# COM_R_manufactured.net
KiCad netlist of a schematic drawn in EAGLE
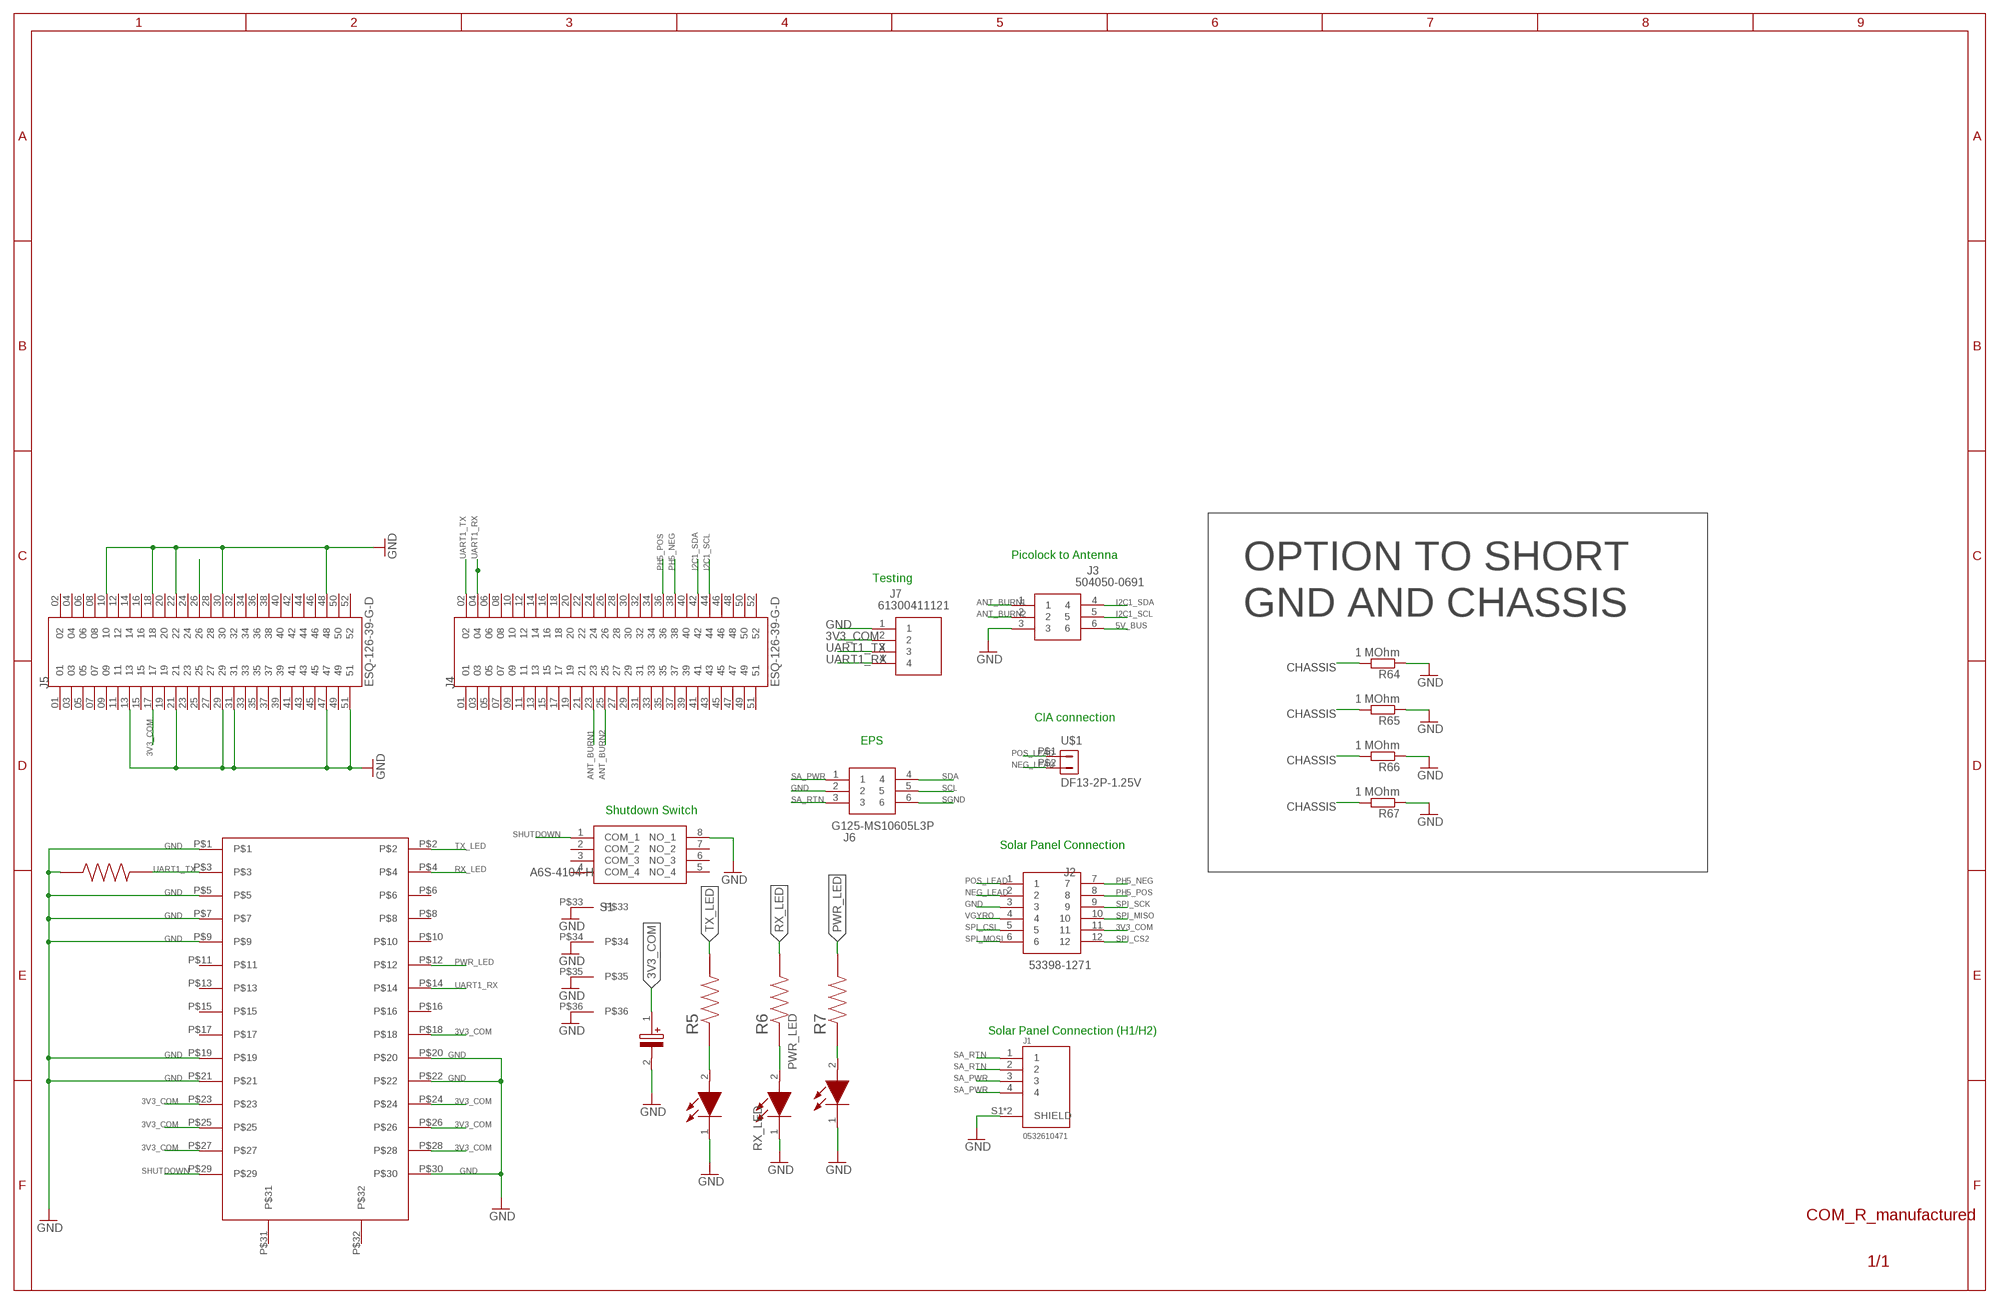
[diagram p0: schematic, sheet 1]

(export (version "E")
  (design (tool "Eeschema 10.0.6"))
  (components
    (comp (ref "C2")
      (value "293D106X0010A2TE3")
      (footprint "eagle-import:CAPPM3216X180N")
      (fields (field (name "MOUSER_PART_NUMBER") "74-293D106X0010A2TE3"))
      (libsource (lib "eagle-import") (part "293D106X0010A2TE3"))
    )
    (comp (ref "J1")
      (value "0532610471")
      (footprint "eagle-import:MOLEX_0532610471")
      (fields (field (name "MF") "Molex"))
      (libsource (lib "eagle-import") (part "0532610471"))
    )
    (comp (ref "J2")
      (value "53398-1271")
      (footprint "eagle-import:53398-1271")
      (fields (field (name "MOUSER_PART_NUMBER") "538-53398-1271"))
      (libsource (lib "eagle-import") (part "53398-1271"))
    )
    (comp (ref "J3")
      (value "504050-0691")
      (footprint "eagle-import:504050-0691_2")
      (fields (field (name "MOUSER_PART_NUMBER") "538-504050-0691"))
      (libsource (lib "eagle-import") (part "504050-0691"))
    )
    (comp (ref "J4")
      (value "ESQ-126-39-G-D")
      (footprint "eagle-import:SAMTEC_ESQ-126-39-G-D")
      (fields (field (name "MF") "Samtec"))
      (libsource (lib "eagle-import") (part "ESQ-126-39-G-D"))
    )
    (comp (ref "J5")
      (value "ESQ-126-39-G-D")
      (footprint "eagle-import:SAMTEC_ESQ-126-39-G-D")
      (fields (field (name "MF") "Samtec"))
      (libsource (lib "eagle-import") (part "ESQ-126-39-G-D"))
    )
    (comp (ref "J6")
      (value "G125-MS10605L3P")
      (footprint "eagle-import:G125-MS10605L3P")
      (fields (field (name "MOUSER_PART_NUMBER") "855-G125-MS10605L3P"))
      (libsource (lib "eagle-import") (part "G125-MS10605L3P"))
    )
    (comp (ref "J7")
      (value "61300411121")
      (footprint "eagle-import:HDRV4W95P0X254_1X4_1016X254X85")
      (fields (field (name "MOUSER_PART_NUMBER") "710-61300411121"))
      (libsource (lib "eagle-import") (part "61300411121"))
    )
    (comp (ref "PWR_LED")
      (value "HSMQ-C170-T0000")
      (footprint "eagle-import:LEDC2012X90N")
      (fields (field (name "MOUSER_PART_NUMBER") "630-HSMQ-C170-T0000"))
      (libsource (lib "eagle-import") (part "HSMQ-C170-T0000"))
    )
    (comp (ref "R3")
      (value "TNPW080510K0BETY")
      (footprint "eagle-import:RESC2012X55N")
      (fields (field (name "DIGI-KEY_PART_NUMBER") "541-3913-1-ND") (field (name "MF") "Vishay"))
      (libsource (lib "eagle-import") (part "TNPW080510K0BETY"))
    )
    (comp (ref "R5")
      (value "Y40621K00000Q0R")
      (footprint "eagle-import:RESC2012X64N")
      (fields (field (name "DIGI-KEY_PART_NUMBER") "Y4062-1.0KACT-ND") (field (name "MF") "Vishay"))
      (libsource (lib "eagle-import") (part "Y40621K00000Q0R"))
    )
    (comp (ref "R6")
      (value "Y40621K00000Q0R")
      (footprint "eagle-import:RESC2012X64N")
      (fields (field (name "DIGI-KEY_PART_NUMBER") "Y4062-1.0KACT-ND") (field (name "MF") "Vishay"))
      (libsource (lib "eagle-import") (part "Y40621K00000Q0R"))
    )
    (comp (ref "R7")
      (value "Y40621K00000Q0R")
      (footprint "eagle-import:RESC2012X64N")
      (fields (field (name "DIGI-KEY_PART_NUMBER") "Y4062-1.0KACT-ND") (field (name "MF") "Vishay"))
      (libsource (lib "eagle-import") (part "Y40621K00000Q0R"))
    )
    (comp (ref "R64")
      (value "1 MOhm")
      (footprint "eagle-import:R0805")
      (libsource (lib "eagle-import") (part "R-EU_R0805"))
    )
    (comp (ref "R65")
      (value "1 MOhm")
      (footprint "eagle-import:R0805")
      (libsource (lib "eagle-import") (part "R-EU_R0805"))
    )
    (comp (ref "R66")
      (value "1 MOhm")
      (footprint "eagle-import:R0805")
      (libsource (lib "eagle-import") (part "R-EU_R0805"))
    )
    (comp (ref "R67")
      (value "1 MOhm")
      (footprint "eagle-import:R0805")
      (libsource (lib "eagle-import") (part "R-EU_R0805"))
    )
    (comp (ref "RX_LED")
      (value "HSMQ-C170-T0000")
      (footprint "eagle-import:LEDC2012X90N")
      (fields (field (name "MOUSER_PART_NUMBER") "630-HSMQ-C170-T0000"))
      (libsource (lib "eagle-import") (part "HSMQ-C170-T0000"))
    )
    (comp (ref "S1")
      (value "A6S-4104-H")
      (footprint "eagle-import:A6S4104H")
      (fields (field (name "MOUSER_PART_NUMBER") "653-A6S-4104-H"))
      (libsource (lib "eagle-import") (part "A6S-4104-H"))
    )
    (comp (ref "TX_LED")
      (value "HSMQ-C170-T0000")
      (footprint "eagle-import:LEDC2012X90N")
      (fields (field (name "MOUSER_PART_NUMBER") "630-HSMQ-C170-T0000"))
      (libsource (lib "eagle-import") (part "HSMQ-C170-T0000"))
    )
    (comp (ref "U$1")
      (value "DF13-2P-1.25V")
      (footprint "eagle-import:DF13C-2P-1.25V")
      (libsource (lib "eagle-import") (part "DF13-2P-1.25V"))
    )
    (comp (ref "U$3")
      (value "XDLRADIOCONNECTORBREAKOUT_KYOCERA_5046_30PIN")
      (footprint "eagle-import:XDLRADIOCONNECTORBREAKOUT_KYOCERA_5046_30PIN")
      (libsource (lib "eagle-import") (part "XDLRADIOCONNECTORBREAKOUT_KYOCERA_5046_30PIN"))
    )
  )
  (nets
    (net (code "1") (name "/5V_BUS") (class "Default")
      (node (ref "J3") (pin "6") (pinfunction "6_6") (pintype "bidirectional"))
      (node (ref "J5") (pin "26") (pinfunction "26_26") (pintype "passive"))
    )
    (net (code "2") (name "/ANT_BURN1") (class "Default")
      (node (ref "J3") (pin "1") (pinfunction "1_1") (pintype "bidirectional"))
      (node (ref "J4") (pin "23") (pinfunction "23_23") (pintype "passive"))
    )
    (net (code "3") (name "/ANT_BURN2") (class "Default")
      (node (ref "J3") (pin "2") (pinfunction "2_2") (pintype "bidirectional"))
      (node (ref "J4") (pin "25") (pinfunction "25_25") (pintype "passive"))
    )
    (net (code "4") (name "/CHASSIS") (class "Default")
      (node (ref "R64") (pin "2") (pinfunction "2_2") (pintype "passive"))
      (node (ref "R65") (pin "2") (pinfunction "2_2") (pintype "passive"))
      (node (ref "R66") (pin "2") (pinfunction "2_2") (pintype "passive"))
      (node (ref "R67") (pin "2") (pinfunction "2_2") (pintype "passive"))
    )
    (net (code "5") (name "/I2C1_SCL") (class "Default")
      (node (ref "J3") (pin "5") (pinfunction "5_5") (pintype "bidirectional"))
      (node (ref "J4") (pin "44") (pinfunction "44_44") (pintype "passive"))
    )
    (net (code "6") (name "/I2C1_SDA") (class "Default")
      (node (ref "J3") (pin "4") (pinfunction "4_4") (pintype "bidirectional"))
      (node (ref "J4") (pin "42") (pinfunction "42_42") (pintype "passive"))
    )
    (net (code "7") (name "/NEG_LEAD") (class "Default")
      (node (ref "J2") (pin "2") (pinfunction "2_2") (pintype "bidirectional"))
      (node (ref "U$1") (pin "P$2") (pinfunction "2_P$2") (pintype "passive"))
    )
    (net (code "8") (name "/PH5_NEG") (class "Default")
      (node (ref "J2") (pin "7") (pinfunction "7_7") (pintype "bidirectional"))
      (node (ref "J4") (pin "38") (pinfunction "38_38") (pintype "passive"))
    )
    (net (code "9") (name "/PH5_POS") (class "Default")
      (node (ref "J2") (pin "8") (pinfunction "8_8") (pintype "bidirectional"))
      (node (ref "J4") (pin "36") (pinfunction "36_36") (pintype "passive"))
    )
    (net (code "10") (name "/POS_LEAD") (class "Default")
      (node (ref "J2") (pin "1") (pinfunction "1_1") (pintype "bidirectional"))
      (node (ref "U$1") (pin "P$1") (pinfunction "1_P$1") (pintype "passive"))
    )
    (net (code "11") (name "/SA_PWR") (class "Default")
      (node (ref "J1") (pin "3") (pinfunction "3_3") (pintype "passive"))
      (node (ref "J1") (pin "4") (pinfunction "4_4") (pintype "passive"))
      (node (ref "J6") (pin "1") (pinfunction "1_1") (pintype "bidirectional"))
    )
    (net (code "12") (name "/SA_RTN") (class "Default")
      (node (ref "J1") (pin "1") (pinfunction "1_1") (pintype "passive"))
      (node (ref "J1") (pin "2") (pinfunction "2_2") (pintype "passive"))
      (node (ref "J6") (pin "3") (pinfunction "3_3") (pintype "bidirectional"))
    )
    (net (code "13") (name "/SCL") (class "Default")
      (node (ref "J6") (pin "5") (pinfunction "5_5") (pintype "bidirectional"))
    )
    (net (code "14") (name "/SDA") (class "Default")
      (node (ref "J6") (pin "4") (pinfunction "4_4") (pintype "bidirectional"))
    )
    (net (code "15") (name "/SGND") (class "Default")
      (node (ref "J6") (pin "6") (pinfunction "6_6") (pintype "bidirectional"))
    )
    (net (code "16") (name "/SHUTDOWN") (class "Default")
      (node (ref "S1") (pin "1") (pinfunction "COM_1_1") (pintype "bidirectional"))
      (node (ref "U$3") (pin "P$29") (pinfunction "P$29_P$29") (pintype "bidirectional"))
    )
    (net (code "17") (name "/SPI_CS2") (class "Default")
      (node (ref "J2") (pin "12") (pinfunction "12_12") (pintype "bidirectional"))
    )
    (net (code "18") (name "/SPI_CSI") (class "Default")
      (node (ref "J2") (pin "5") (pinfunction "5_5") (pintype "bidirectional"))
    )
    (net (code "19") (name "/SPI_MISO") (class "Default")
      (node (ref "J2") (pin "10") (pinfunction "10_10") (pintype "bidirectional"))
    )
    (net (code "20") (name "/SPI_MOSI") (class "Default")
      (node (ref "J2") (pin "6") (pinfunction "6_6") (pintype "bidirectional"))
    )
    (net (code "21") (name "/SPI_SCK") (class "Default")
      (node (ref "J2") (pin "9") (pinfunction "9_9") (pintype "bidirectional"))
    )
    (net (code "22") (name "/UART1_RX") (class "Default")
      (node (ref "J4") (pin "04") (pinfunction "04_04") (pintype "passive"))
      (node (ref "J7") (pin "4") (pinfunction "4_4") (pintype "bidirectional"))
      (node (ref "U$3") (pin "P$14") (pinfunction "P$14_P$14") (pintype "bidirectional"))
    )
    (net (code "23") (name "/UART1_TX") (class "Default")
      (node (ref "J4") (pin "02") (pinfunction "02_02") (pintype "passive"))
      (node (ref "J7") (pin "3") (pinfunction "3_3") (pintype "bidirectional"))
      (node (ref "R3") (pin "2") (pinfunction "2_2") (pintype "passive"))
      (node (ref "U$3") (pin "P$3") (pinfunction "P$3_P$3") (pintype "bidirectional"))
    )
    (net (code "24") (name "/VGYRO") (class "Default")
      (node (ref "J2") (pin "4") (pinfunction "4_4") (pintype "bidirectional"))
    )
    (net (code "25") (name "3V3_COM") (class "Default")
      (node (ref "C2") (pin "1") (pinfunction "+_1") (pintype "bidirectional"))
      (node (ref "J2") (pin "11") (pinfunction "11_11") (pintype "bidirectional"))
      (node (ref "J5") (pin "17") (pinfunction "17_17") (pintype "passive"))
      (node (ref "J7") (pin "2") (pinfunction "2_2") (pintype "bidirectional"))
      (node (ref "U$3") (pin "P$18") (pinfunction "P$18_P$18") (pintype "bidirectional"))
      (node (ref "U$3") (pin "P$23") (pinfunction "P$23_P$23") (pintype "bidirectional"))
      (node (ref "U$3") (pin "P$24") (pinfunction "P$24_P$24") (pintype "bidirectional"))
      (node (ref "U$3") (pin "P$25") (pinfunction "P$25_P$25") (pintype "bidirectional"))
      (node (ref "U$3") (pin "P$26") (pinfunction "P$26_P$26") (pintype "bidirectional"))
      (node (ref "U$3") (pin "P$27") (pinfunction "P$27_P$27") (pintype "bidirectional"))
      (node (ref "U$3") (pin "P$28") (pinfunction "P$28_P$28") (pintype "bidirectional"))
    )
    (net (code "26") (name "GND") (class "Default")
      (node (ref "C2") (pin "2") (pinfunction "-_2") (pintype "bidirectional"))
      (node (ref "J1") (pin "S1") (pinfunction "SHIELD_S1") (pintype "passive"))
      (node (ref "J1") (pin "S2") (pinfunction "SHIELD_S2") (pintype "passive"))
      (node (ref "J2") (pin "3") (pinfunction "3_3") (pintype "bidirectional"))
      (node (ref "J3") (pin "3") (pinfunction "3_3") (pintype "bidirectional"))
      (node (ref "J5") (pin "10") (pinfunction "10_10") (pintype "passive"))
      (node (ref "J5") (pin "13") (pinfunction "13_13") (pintype "passive"))
      (node (ref "J5") (pin "18") (pinfunction "18_18") (pintype "passive"))
      (node (ref "J5") (pin "21") (pinfunction "21_21") (pintype "passive"))
      (node (ref "J5") (pin "22") (pinfunction "22_22") (pintype "passive"))
      (node (ref "J5") (pin "29") (pinfunction "29_29") (pintype "passive"))
      (node (ref "J5") (pin "30") (pinfunction "30_30") (pintype "passive"))
      (node (ref "J5") (pin "31") (pinfunction "31_31") (pintype "passive"))
      (node (ref "J5") (pin "47") (pinfunction "47_47") (pintype "passive"))
      (node (ref "J5") (pin "48") (pinfunction "48_48") (pintype "passive"))
      (node (ref "J5") (pin "51") (pinfunction "51_51") (pintype "passive"))
      (node (ref "J6") (pin "2") (pinfunction "2_2") (pintype "bidirectional"))
      (node (ref "J7") (pin "1") (pinfunction "1_1") (pintype "bidirectional"))
      (node (ref "PWR_LED") (pin "1") (pinfunction "K_1") (pintype "bidirectional"))
      (node (ref "R3") (pin "1") (pinfunction "1_1") (pintype "passive"))
      (node (ref "R64") (pin "1") (pinfunction "1_1") (pintype "passive"))
      (node (ref "R65") (pin "1") (pinfunction "1_1") (pintype "passive"))
      (node (ref "R66") (pin "1") (pinfunction "1_1") (pintype "passive"))
      (node (ref "R67") (pin "1") (pinfunction "1_1") (pintype "passive"))
      (node (ref "RX_LED") (pin "1") (pinfunction "K_1") (pintype "bidirectional"))
      (node (ref "S1") (pin "8") (pinfunction "NO_1_8") (pintype "bidirectional"))
      (node (ref "TX_LED") (pin "1") (pinfunction "K_1") (pintype "bidirectional"))
      (node (ref "U$3") (pin "P$1") (pinfunction "P$1_P$1") (pintype "bidirectional"))
      (node (ref "U$3") (pin "P$19") (pinfunction "P$19_P$19") (pintype "bidirectional"))
      (node (ref "U$3") (pin "P$20") (pinfunction "P$20_P$20") (pintype "bidirectional"))
      (node (ref "U$3") (pin "P$21") (pinfunction "P$21_P$21") (pintype "bidirectional"))
      (node (ref "U$3") (pin "P$22") (pinfunction "P$22_P$22") (pintype "bidirectional"))
      (node (ref "U$3") (pin "P$30") (pinfunction "P$30_P$30") (pintype "bidirectional"))
      (node (ref "U$3") (pin "P$33") (pinfunction "P$33_P$33") (pintype "bidirectional"))
      (node (ref "U$3") (pin "P$34") (pinfunction "P$34_P$34") (pintype "bidirectional"))
      (node (ref "U$3") (pin "P$35") (pinfunction "P$35_P$35") (pintype "bidirectional"))
      (node (ref "U$3") (pin "P$36") (pinfunction "P$36_P$36") (pintype "bidirectional"))
      (node (ref "U$3") (pin "P$5") (pinfunction "P$5_P$5") (pintype "bidirectional"))
      (node (ref "U$3") (pin "P$7") (pinfunction "P$7_P$7") (pintype "bidirectional"))
      (node (ref "U$3") (pin "P$9") (pinfunction "P$9_P$9") (pintype "bidirectional"))
    )
    (net (code "27") (name "Net-(PWR_LED-A)") (class "Default")
      (node (ref "PWR_LED") (pin "2") (pinfunction "A_2") (pintype "bidirectional"))
      (node (ref "R7") (pin "1") (pinfunction "1_1") (pintype "passive"))
    )
    (net (code "28") (name "Net-(RX_LED-A)") (class "Default")
      (node (ref "R6") (pin "1") (pinfunction "1_1") (pintype "passive"))
      (node (ref "RX_LED") (pin "2") (pinfunction "A_2") (pintype "bidirectional"))
    )
    (net (code "29") (name "Net-(TX_LED-A)") (class "Default")
      (node (ref "R5") (pin "1") (pinfunction "1_1") (pintype "passive"))
      (node (ref "TX_LED") (pin "2") (pinfunction "A_2") (pintype "bidirectional"))
    )
    (net (code "30") (name "PWR_LED") (class "Default")
      (node (ref "R7") (pin "2") (pinfunction "2_2") (pintype "passive"))
      (node (ref "U$3") (pin "P$12") (pinfunction "P$12_P$12") (pintype "bidirectional"))
    )
    (net (code "31") (name "RX_LED") (class "Default")
      (node (ref "R6") (pin "2") (pinfunction "2_2") (pintype "passive"))
      (node (ref "U$3") (pin "P$4") (pinfunction "P$4_P$4") (pintype "bidirectional"))
    )
    (net (code "32") (name "TX_LED") (class "Default")
      (node (ref "R5") (pin "2") (pinfunction "2_2") (pintype "passive"))
      (node (ref "U$3") (pin "P$2") (pinfunction "P$2_P$2") (pintype "bidirectional"))
    )
    (net (code "33") (name "unconnected-(J4-Pad01)") (class "Default")
      (node (ref "J4") (pin "01") (pinfunction "01_01") (pintype "passive"))
    )
    (net (code "34") (name "unconnected-(J4-Pad03)") (class "Default")
      (node (ref "J4") (pin "03") (pinfunction "03_03") (pintype "passive"))
    )
    (net (code "35") (name "unconnected-(J4-Pad05)") (class "Default")
      (node (ref "J4") (pin "05") (pinfunction "05_05") (pintype "passive"))
    )
    (net (code "36") (name "unconnected-(J4-Pad06)") (class "Default")
      (node (ref "J4") (pin "06") (pinfunction "06_06") (pintype "passive"))
    )
    (net (code "37") (name "unconnected-(J4-Pad07)") (class "Default")
      (node (ref "J4") (pin "07") (pinfunction "07_07") (pintype "passive"))
    )
    (net (code "38") (name "unconnected-(J4-Pad08)") (class "Default")
      (node (ref "J4") (pin "08") (pinfunction "08_08") (pintype "passive"))
    )
    (net (code "39") (name "unconnected-(J4-Pad09)") (class "Default")
      (node (ref "J4") (pin "09") (pinfunction "09_09") (pintype "passive"))
    )
    (net (code "40") (name "unconnected-(J4-Pad10)") (class "Default")
      (node (ref "J4") (pin "10") (pinfunction "10_10") (pintype "passive"))
    )
    (net (code "41") (name "unconnected-(J4-Pad11)") (class "Default")
      (node (ref "J4") (pin "11") (pinfunction "11_11") (pintype "passive"))
    )
    (net (code "42") (name "unconnected-(J4-Pad12)") (class "Default")
      (node (ref "J4") (pin "12") (pinfunction "12_12") (pintype "passive"))
    )
    (net (code "43") (name "unconnected-(J4-Pad13)") (class "Default")
      (node (ref "J4") (pin "13") (pinfunction "13_13") (pintype "passive"))
    )
    (net (code "44") (name "unconnected-(J4-Pad14)") (class "Default")
      (node (ref "J4") (pin "14") (pinfunction "14_14") (pintype "passive"))
    )
    (net (code "45") (name "unconnected-(J4-Pad15)") (class "Default")
      (node (ref "J4") (pin "15") (pinfunction "15_15") (pintype "passive"))
    )
    (net (code "46") (name "unconnected-(J4-Pad16)") (class "Default")
      (node (ref "J4") (pin "16") (pinfunction "16_16") (pintype "passive"))
    )
    (net (code "47") (name "unconnected-(J4-Pad17)") (class "Default")
      (node (ref "J4") (pin "17") (pinfunction "17_17") (pintype "passive"))
    )
    (net (code "48") (name "unconnected-(J4-Pad18)") (class "Default")
      (node (ref "J4") (pin "18") (pinfunction "18_18") (pintype "passive"))
    )
    (net (code "49") (name "unconnected-(J4-Pad19)") (class "Default")
      (node (ref "J4") (pin "19") (pinfunction "19_19") (pintype "passive"))
    )
    (net (code "50") (name "unconnected-(J4-Pad20)") (class "Default")
      (node (ref "J4") (pin "20") (pinfunction "20_20") (pintype "passive"))
    )
    (net (code "51") (name "unconnected-(J4-Pad21)") (class "Default")
      (node (ref "J4") (pin "21") (pinfunction "21_21") (pintype "passive"))
    )
    (net (code "52") (name "unconnected-(J4-Pad22)") (class "Default")
      (node (ref "J4") (pin "22") (pinfunction "22_22") (pintype "passive"))
    )
    (net (code "53") (name "unconnected-(J4-Pad24)") (class "Default")
      (node (ref "J4") (pin "24") (pinfunction "24_24") (pintype "passive"))
    )
    (net (code "54") (name "unconnected-(J4-Pad26)") (class "Default")
      (node (ref "J4") (pin "26") (pinfunction "26_26") (pintype "passive"))
    )
    (net (code "55") (name "unconnected-(J4-Pad27)") (class "Default")
      (node (ref "J4") (pin "27") (pinfunction "27_27") (pintype "passive"))
    )
    (net (code "56") (name "unconnected-(J4-Pad28)") (class "Default")
      (node (ref "J4") (pin "28") (pinfunction "28_28") (pintype "passive"))
    )
    (net (code "57") (name "unconnected-(J4-Pad29)") (class "Default")
      (node (ref "J4") (pin "29") (pinfunction "29_29") (pintype "passive"))
    )
    (net (code "58") (name "unconnected-(J4-Pad30)") (class "Default")
      (node (ref "J4") (pin "30") (pinfunction "30_30") (pintype "passive"))
    )
    (net (code "59") (name "unconnected-(J4-Pad31)") (class "Default")
      (node (ref "J4") (pin "31") (pinfunction "31_31") (pintype "passive"))
    )
    (net (code "60") (name "unconnected-(J4-Pad32)") (class "Default")
      (node (ref "J4") (pin "32") (pinfunction "32_32") (pintype "passive"))
    )
    (net (code "61") (name "unconnected-(J4-Pad33)") (class "Default")
      (node (ref "J4") (pin "33") (pinfunction "33_33") (pintype "passive"))
    )
    (net (code "62") (name "unconnected-(J4-Pad34)") (class "Default")
      (node (ref "J4") (pin "34") (pinfunction "34_34") (pintype "passive"))
    )
    (net (code "63") (name "unconnected-(J4-Pad35)") (class "Default")
      (node (ref "J4") (pin "35") (pinfunction "35_35") (pintype "passive"))
    )
    (net (code "64") (name "unconnected-(J4-Pad37)") (class "Default")
      (node (ref "J4") (pin "37") (pinfunction "37_37") (pintype "passive"))
    )
    (net (code "65") (name "unconnected-(J4-Pad39)") (class "Default")
      (node (ref "J4") (pin "39") (pinfunction "39_39") (pintype "passive"))
    )
    (net (code "66") (name "unconnected-(J4-Pad40)") (class "Default")
      (node (ref "J4") (pin "40") (pinfunction "40_40") (pintype "passive"))
    )
    (net (code "67") (name "unconnected-(J4-Pad41)") (class "Default")
      (node (ref "J4") (pin "41") (pinfunction "41_41") (pintype "passive"))
    )
    (net (code "68") (name "unconnected-(J4-Pad43)") (class "Default")
      (node (ref "J4") (pin "43") (pinfunction "43_43") (pintype "passive"))
    )
    (net (code "69") (name "unconnected-(J4-Pad45)") (class "Default")
      (node (ref "J4") (pin "45") (pinfunction "45_45") (pintype "passive"))
    )
    (net (code "70") (name "unconnected-(J4-Pad46)") (class "Default")
      (node (ref "J4") (pin "46") (pinfunction "46_46") (pintype "passive"))
    )
    (net (code "71") (name "unconnected-(J4-Pad47)") (class "Default")
      (node (ref "J4") (pin "47") (pinfunction "47_47") (pintype "passive"))
    )
    (net (code "72") (name "unconnected-(J4-Pad48)") (class "Default")
      (node (ref "J4") (pin "48") (pinfunction "48_48") (pintype "passive"))
    )
    (net (code "73") (name "unconnected-(J4-Pad49)") (class "Default")
      (node (ref "J4") (pin "49") (pinfunction "49_49") (pintype "passive"))
    )
    (net (code "74") (name "unconnected-(J4-Pad50)") (class "Default")
      (node (ref "J4") (pin "50") (pinfunction "50_50") (pintype "passive"))
    )
    (net (code "75") (name "unconnected-(J4-Pad51)") (class "Default")
      (node (ref "J4") (pin "51") (pinfunction "51_51") (pintype "passive"))
    )
    (net (code "76") (name "unconnected-(J4-Pad52)") (class "Default")
      (node (ref "J4") (pin "52") (pinfunction "52_52") (pintype "passive"))
    )
    (net (code "77") (name "unconnected-(J5-Pad01)") (class "Default")
      (node (ref "J5") (pin "01") (pinfunction "01_01") (pintype "passive"))
    )
    (net (code "78") (name "unconnected-(J5-Pad02)") (class "Default")
      (node (ref "J5") (pin "02") (pinfunction "02_02") (pintype "passive"))
    )
    (net (code "79") (name "unconnected-(J5-Pad03)") (class "Default")
      (node (ref "J5") (pin "03") (pinfunction "03_03") (pintype "passive"))
    )
    (net (code "80") (name "unconnected-(J5-Pad04)") (class "Default")
      (node (ref "J5") (pin "04") (pinfunction "04_04") (pintype "passive"))
    )
    (net (code "81") (name "unconnected-(J5-Pad05)") (class "Default")
      (node (ref "J5") (pin "05") (pinfunction "05_05") (pintype "passive"))
    )
    (net (code "82") (name "unconnected-(J5-Pad06)") (class "Default")
      (node (ref "J5") (pin "06") (pinfunction "06_06") (pintype "passive"))
    )
    (net (code "83") (name "unconnected-(J5-Pad07)") (class "Default")
      (node (ref "J5") (pin "07") (pinfunction "07_07") (pintype "passive"))
    )
    (net (code "84") (name "unconnected-(J5-Pad08)") (class "Default")
      (node (ref "J5") (pin "08") (pinfunction "08_08") (pintype "passive"))
    )
    (net (code "85") (name "unconnected-(J5-Pad09)") (class "Default")
      (node (ref "J5") (pin "09") (pinfunction "09_09") (pintype "passive"))
    )
    (net (code "86") (name "unconnected-(J5-Pad11)") (class "Default")
      (node (ref "J5") (pin "11") (pinfunction "11_11") (pintype "passive"))
    )
    (net (code "87") (name "unconnected-(J5-Pad12)") (class "Default")
      (node (ref "J5") (pin "12") (pinfunction "12_12") (pintype "passive"))
    )
    (net (code "88") (name "unconnected-(J5-Pad14)") (class "Default")
      (node (ref "J5") (pin "14") (pinfunction "14_14") (pintype "passive"))
    )
    (net (code "89") (name "unconnected-(J5-Pad15)") (class "Default")
      (node (ref "J5") (pin "15") (pinfunction "15_15") (pintype "passive"))
    )
    (net (code "90") (name "unconnected-(J5-Pad16)") (class "Default")
      (node (ref "J5") (pin "16") (pinfunction "16_16") (pintype "passive"))
    )
    (net (code "91") (name "unconnected-(J5-Pad19)") (class "Default")
      (node (ref "J5") (pin "19") (pinfunction "19_19") (pintype "passive"))
    )
    (net (code "92") (name "unconnected-(J5-Pad20)") (class "Default")
      (node (ref "J5") (pin "20") (pinfunction "20_20") (pintype "passive"))
    )
    (net (code "93") (name "unconnected-(J5-Pad23)") (class "Default")
      (node (ref "J5") (pin "23") (pinfunction "23_23") (pintype "passive"))
    )
    (net (code "94") (name "unconnected-(J5-Pad24)") (class "Default")
      (node (ref "J5") (pin "24") (pinfunction "24_24") (pintype "passive"))
    )
    (net (code "95") (name "unconnected-(J5-Pad25)") (class "Default")
      (node (ref "J5") (pin "25") (pinfunction "25_25") (pintype "passive"))
    )
    (net (code "96") (name "unconnected-(J5-Pad27)") (class "Default")
      (node (ref "J5") (pin "27") (pinfunction "27_27") (pintype "passive"))
    )
    (net (code "97") (name "unconnected-(J5-Pad28)") (class "Default")
      (node (ref "J5") (pin "28") (pinfunction "28_28") (pintype "passive"))
    )
    (net (code "98") (name "unconnected-(J5-Pad32)") (class "Default")
      (node (ref "J5") (pin "32") (pinfunction "32_32") (pintype "passive"))
    )
    (net (code "99") (name "unconnected-(J5-Pad33)") (class "Default")
      (node (ref "J5") (pin "33") (pinfunction "33_33") (pintype "passive"))
    )
    (net (code "100") (name "unconnected-(J5-Pad34)") (class "Default")
      (node (ref "J5") (pin "34") (pinfunction "34_34") (pintype "passive"))
    )
    (net (code "101") (name "unconnected-(J5-Pad35)") (class "Default")
      (node (ref "J5") (pin "35") (pinfunction "35_35") (pintype "passive"))
    )
    (net (code "102") (name "unconnected-(J5-Pad36)") (class "Default")
      (node (ref "J5") (pin "36") (pinfunction "36_36") (pintype "passive"))
    )
    (net (code "103") (name "unconnected-(J5-Pad37)") (class "Default")
      (node (ref "J5") (pin "37") (pinfunction "37_37") (pintype "passive"))
    )
    (net (code "104") (name "unconnected-(J5-Pad38)") (class "Default")
      (node (ref "J5") (pin "38") (pinfunction "38_38") (pintype "passive"))
    )
    (net (code "105") (name "unconnected-(J5-Pad39)") (class "Default")
      (node (ref "J5") (pin "39") (pinfunction "39_39") (pintype "passive"))
    )
    (net (code "106") (name "unconnected-(J5-Pad40)") (class "Default")
      (node (ref "J5") (pin "40") (pinfunction "40_40") (pintype "passive"))
    )
    (net (code "107") (name "unconnected-(J5-Pad41)") (class "Default")
      (node (ref "J5") (pin "41") (pinfunction "41_41") (pintype "passive"))
    )
    (net (code "108") (name "unconnected-(J5-Pad42)") (class "Default")
      (node (ref "J5") (pin "42") (pinfunction "42_42") (pintype "passive"))
    )
    (net (code "109") (name "unconnected-(J5-Pad43)") (class "Default")
      (node (ref "J5") (pin "43") (pinfunction "43_43") (pintype "passive"))
    )
    (net (code "110") (name "unconnected-(J5-Pad44)") (class "Default")
      (node (ref "J5") (pin "44") (pinfunction "44_44") (pintype "passive"))
    )
    (net (code "111") (name "unconnected-(J5-Pad45)") (class "Default")
      (node (ref "J5") (pin "45") (pinfunction "45_45") (pintype "passive"))
    )
    (net (code "112") (name "unconnected-(J5-Pad46)") (class "Default")
      (node (ref "J5") (pin "46") (pinfunction "46_46") (pintype "passive"))
    )
    (net (code "113") (name "unconnected-(J5-Pad49)") (class "Default")
      (node (ref "J5") (pin "49") (pinfunction "49_49") (pintype "passive"))
    )
    (net (code "114") (name "unconnected-(J5-Pad50)") (class "Default")
      (node (ref "J5") (pin "50") (pinfunction "50_50") (pintype "passive"))
    )
    (net (code "115") (name "unconnected-(J5-Pad52)") (class "Default")
      (node (ref "J5") (pin "52") (pinfunction "52_52") (pintype "passive"))
    )
    (net (code "116") (name "unconnected-(S1-COM_2-Pad2)") (class "Default")
      (node (ref "S1") (pin "2") (pinfunction "COM_2_2") (pintype "bidirectional"))
    )
    (net (code "117") (name "unconnected-(S1-COM_3-Pad3)") (class "Default")
      (node (ref "S1") (pin "3") (pinfunction "COM_3_3") (pintype "bidirectional"))
    )
    (net (code "118") (name "unconnected-(S1-COM_4-Pad4)") (class "Default")
      (node (ref "S1") (pin "4") (pinfunction "COM_4_4") (pintype "bidirectional"))
    )
    (net (code "119") (name "unconnected-(S1-NO_2-Pad7)") (class "Default")
      (node (ref "S1") (pin "7") (pinfunction "NO_2_7") (pintype "bidirectional"))
    )
    (net (code "120") (name "unconnected-(S1-NO_3-Pad6)") (class "Default")
      (node (ref "S1") (pin "6") (pinfunction "NO_3_6") (pintype "bidirectional"))
    )
    (net (code "121") (name "unconnected-(S1-NO_4-Pad5)") (class "Default")
      (node (ref "S1") (pin "5") (pinfunction "NO_4_5") (pintype "bidirectional"))
    )
    (net (code "122") (name "unconnected-(U$3-PadP$6)") (class "Default")
      (node (ref "U$3") (pin "P$6") (pinfunction "P$6_P$6") (pintype "bidirectional"))
    )
    (net (code "123") (name "unconnected-(U$3-PadP$8)") (class "Default")
      (node (ref "U$3") (pin "P$8") (pinfunction "P$8_P$8") (pintype "bidirectional"))
    )
    (net (code "124") (name "unconnected-(U$3-PadP$10)") (class "Default")
      (node (ref "U$3") (pin "P$10") (pinfunction "P$10_P$10") (pintype "bidirectional"))
    )
    (net (code "125") (name "unconnected-(U$3-PadP$11)") (class "Default")
      (node (ref "U$3") (pin "P$11") (pinfunction "P$11_P$11") (pintype "bidirectional"))
    )
    (net (code "126") (name "unconnected-(U$3-PadP$13)") (class "Default")
      (node (ref "U$3") (pin "P$13") (pinfunction "P$13_P$13") (pintype "bidirectional"))
    )
    (net (code "127") (name "unconnected-(U$3-PadP$15)") (class "Default")
      (node (ref "U$3") (pin "P$15") (pinfunction "P$15_P$15") (pintype "bidirectional"))
    )
    (net (code "128") (name "unconnected-(U$3-PadP$16)") (class "Default")
      (node (ref "U$3") (pin "P$16") (pinfunction "P$16_P$16") (pintype "bidirectional"))
    )
    (net (code "129") (name "unconnected-(U$3-PadP$17)") (class "Default")
      (node (ref "U$3") (pin "P$17") (pinfunction "P$17_P$17") (pintype "bidirectional"))
    )
    (net (code "130") (name "unconnected-(U$3-PadP$31)") (class "Default")
      (node (ref "U$3") (pin "P$31") (pinfunction "P$31_P$31") (pintype "bidirectional"))
    )
    (net (code "131") (name "unconnected-(U$3-PadP$32)") (class "Default")
      (node (ref "U$3") (pin "P$32") (pinfunction "P$32_P$32") (pintype "bidirectional"))
    )
  )
)
